# DC-PSx.net
KiCad netlist of a schematic drawn in EAGLE
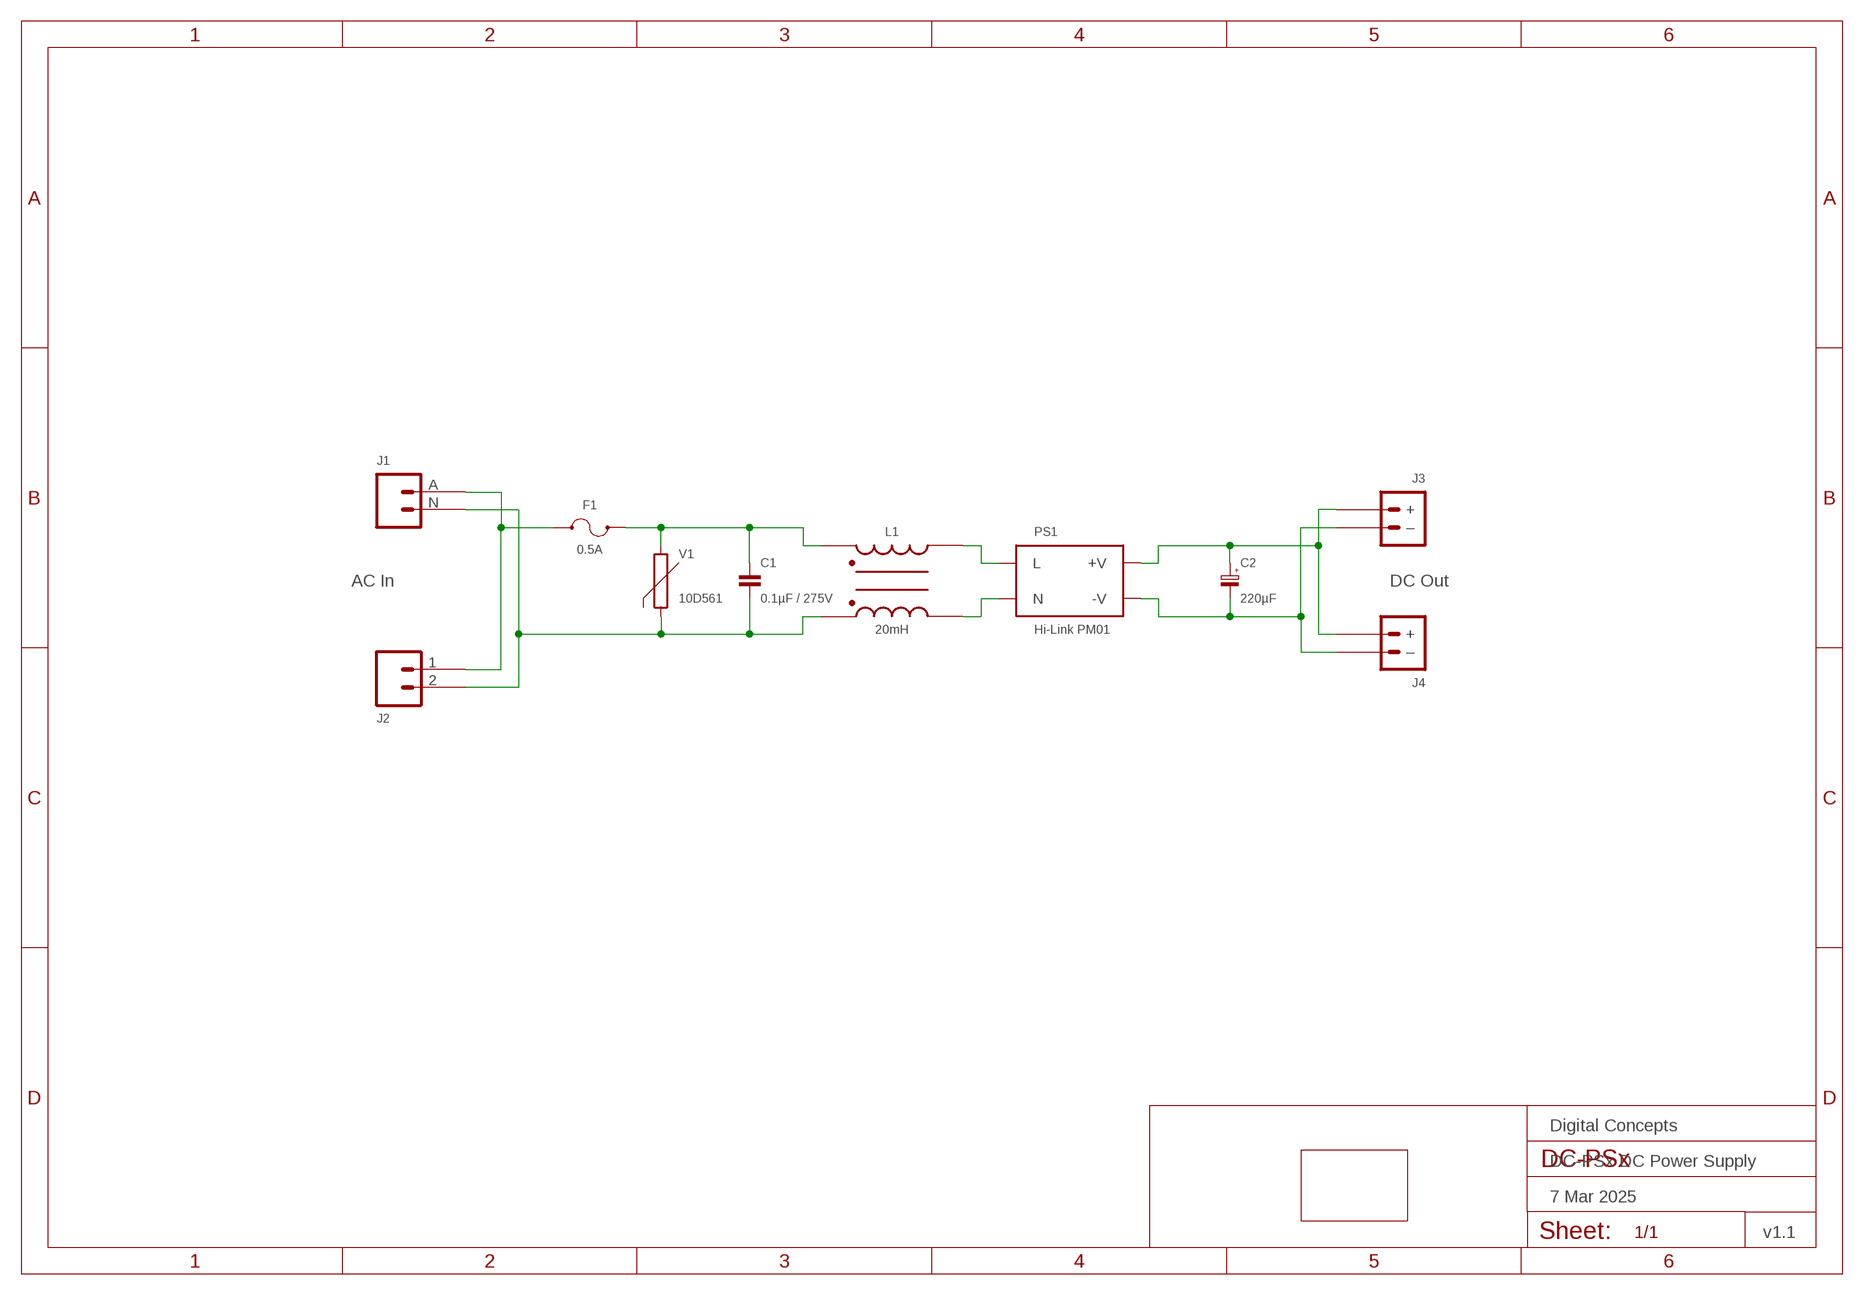
[diagram p0: schematic, sheet 1]

(export (version "E")
  (design (tool "Eeschema 10.0.6"))
  (components
    (comp (ref "C1")
      (value "0.1µF / 275V")
      (footprint "eagle-import:CAPACITOR-TENTA-SUPPRESSION")
      (libsource (lib "eagle-import") (part "CAPACITOR-TENTA-SUPPRESSION"))
    )
    (comp (ref "C2")
      (value "220µF")
      (footprint "eagle-import:E5-10,5")
      (libsource (lib "eagle-import") (part "CAPACITOR-ELECTROLYTICE5-10.5"))
    )
    (comp (ref "F1")
      (value "0.5A")
      (footprint "eagle-import:FUSE-HOLDER-1808")
      (libsource (lib "eagle-import") (part "FUSE-HOLDER-1808"))
    )
    (comp (ref "J1")
      (value "AC In")
      (footprint "eagle-import:DB-03_AC_POWER_SOCKET")
      (libsource (lib "eagle-import") (part "AC_POWER_SOCKET_DB-03"))
    )
    (comp (ref "J2")
      (value "TERMINAL_SCREW_2P_VERTICAL")
      (footprint "eagle-import:TERMINAL-SCREW-2P")
      (libsource (lib "eagle-import") (part "TERMINAL_SCREW_2P_VERTICAL"))
    )
    (comp (ref "J3")
      (value "DC Out")
      (footprint "eagle-import:JST-PH2.0-2-VERTICAL-POWER")
      (libsource (lib "eagle-import") (part "JST-PH2.0-2-VERTICAL-POWER"))
    )
    (comp (ref "J4")
      (value "TERMINAL_SCREW_2P_POWER")
      (footprint "eagle-import:TERMINAL-SCREW-2P")
      (libsource (lib "eagle-import") (part "TERMINAL_SCREW_2P_POWER"))
    )
    (comp (ref "L1")
      (value "20mH")
      (footprint "eagle-import:INDUCTOR-UU9.8")
      (libsource (lib "eagle-import") (part "INDUCTOR-COMMON-MODE-UU9.8"))
    )
    (comp (ref "PCB1")
      (value "PCB-OUTLINE-64X36")
      (footprint "eagle-import:PCB-POWER-SUPPLY-3")
      (libsource (lib "eagle-import") (part "PCB-OUTLINE-64X36"))
    )
    (comp (ref "PS1")
      (value "Hi-Link PM01")
      (footprint "eagle-import:HI-LINK_PM0X")
      (libsource (lib "eagle-import") (part "POWER_SUPPLY-HI-LINK"))
    )
    (comp (ref "V1")
      (value "10D561")
      (footprint "eagle-import:VARISTOR-10D561")
      (libsource (lib "eagle-import") (part "VARISTOR-10D561"))
    )
  )
  (nets
    (net (code "1") (name "Net-(C1-1)") (class "Default")
      (node (ref "C1") (pin "P$1") (pinfunction "1_P$1") (pintype "passive"))
      (node (ref "F1") (pin "P$2") (pinfunction "2_P$2") (pintype "passive"))
      (node (ref "L1") (pin "P$1") (pinfunction "1_P$1") (pintype "passive"))
      (node (ref "V1") (pin "2") (pinfunction "2_2") (pintype "passive"))
    )
    (net (code "2") (name "Net-(C1-2)") (class "Default")
      (node (ref "C1") (pin "P$2") (pinfunction "2_P$2") (pintype "passive"))
      (node (ref "J1") (pin "N") (pinfunction "1_N") (pintype "passive"))
      (node (ref "J2") (pin "2") (pinfunction "2_2") (pintype "passive"))
      (node (ref "L1") (pin "P$4") (pinfunction "4_P$4") (pintype "passive"))
      (node (ref "V1") (pin "1") (pinfunction "1_1") (pintype "passive"))
    )
    (net (code "3") (name "Net-(F1-1)") (class "Default")
      (node (ref "F1") (pin "P$1") (pinfunction "1_P$1") (pintype "passive"))
      (node (ref "J1") (pin "A") (pinfunction "2_A") (pintype "passive"))
      (node (ref "J2") (pin "1") (pinfunction "1_1") (pintype "passive"))
    )
    (net (code "4") (name "Net-(J3-–)") (class "Default")
      (node (ref "C2") (pin "-") (pinfunction "-_-") (pintype "passive"))
      (node (ref "J3") (pin "-") (pinfunction "–_-") (pintype "power_in"))
      (node (ref "J4") (pin "1") (pinfunction "–_1") (pintype "power_in"))
      (node (ref "PS1") (pin "-VO") (pinfunction "-V_-VO") (pintype "power_in"))
    )
    (net (code "5") (name "Net-(J4-+)") (class "Default")
      (node (ref "C2") (pin "+") (pinfunction "+_+") (pintype "passive"))
      (node (ref "J3") (pin "+") (pinfunction "+_+") (pintype "power_in"))
      (node (ref "J4") (pin "2") (pinfunction "+_2") (pintype "power_in"))
      (node (ref "PS1") (pin "+VO") (pinfunction "+V_+VO") (pintype "power_in"))
    )
    (net (code "6") (name "Net-(L1-2)") (class "Default")
      (node (ref "L1") (pin "P$2") (pinfunction "2_P$2") (pintype "passive"))
      (node (ref "PS1") (pin "AC-L") (pinfunction "L_AC-L") (pintype "power_in"))
    )
    (net (code "7") (name "Net-(L1-3)") (class "Default")
      (node (ref "L1") (pin "P$3") (pinfunction "3_P$3") (pintype "passive"))
      (node (ref "PS1") (pin "AC-N") (pinfunction "N_AC-N") (pintype "power_in"))
    )
  )
)
